# utilidong-butt-mk-1_1.net
KiCad netlist of a schematic drawn in EAGLE
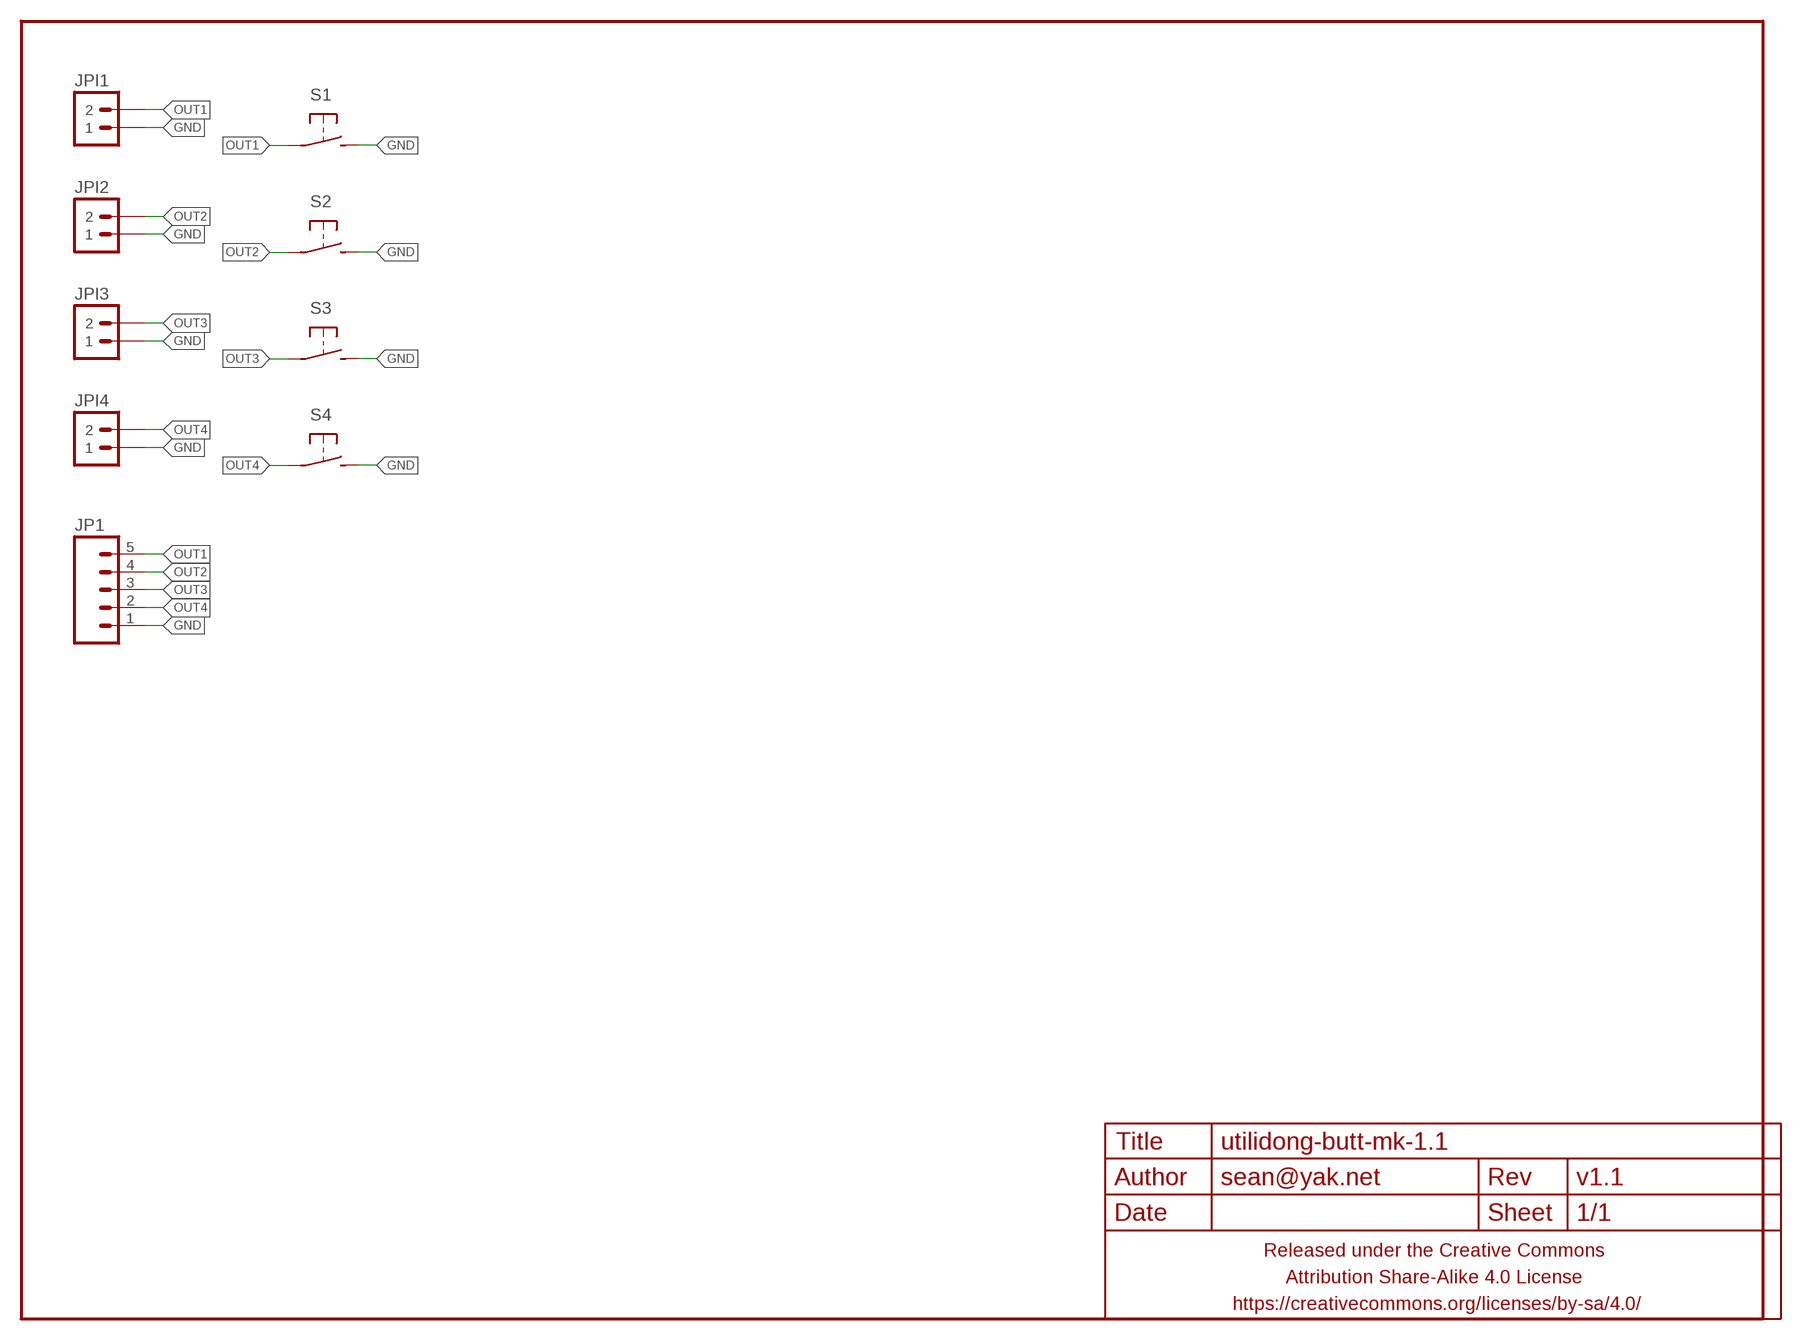
[diagram p0: schematic, sheet 1]

(export (version "E")
  (design (tool "Eeschema 10.0.6"))
  (components
    (comp (ref "FRAME1")
      (value "FRAME-LETTERNO_PACKAGE")
      (footprint "eagle-import:DUMMY")
      (fields (field (name "DESIGNER") "sean@yak.net") (field (name "VERSION") "v1.1"))
      (libsource (lib "eagle-import") (part "FRAME-LETTERNO_PACKAGE"))
    )
    (comp (ref "JP1")
      (value "M05JST-PH-VERT-PTH")
      (footprint "eagle-import:JST-5-PH-VERT-PTH")
      (libsource (lib "eagle-import") (part "M05JST-PH-VERT-PTH"))
    )
    (comp (ref "JPI1")
      (value "M02PTH-CENTERED")
      (footprint "eagle-import:1X02-CENTER")
      (libsource (lib "eagle-import") (part "M02PTH-CENTERED"))
    )
    (comp (ref "JPI2")
      (value "M02PTH-CENTERED")
      (footprint "eagle-import:1X02-CENTER")
      (libsource (lib "eagle-import") (part "M02PTH-CENTERED"))
    )
    (comp (ref "JPI3")
      (value "M02PTH-CENTERED")
      (footprint "eagle-import:1X02-CENTER")
      (libsource (lib "eagle-import") (part "M02PTH-CENTERED"))
    )
    (comp (ref "JPI4")
      (value "M02PTH-CENTERED")
      (footprint "eagle-import:1X02-CENTER")
      (libsource (lib "eagle-import") (part "M02PTH-CENTERED"))
    )
    (comp (ref "S1")
      (value "SPST-NO-TACT6MM-PTH-SMALL-PADS")
      (footprint "eagle-import:DTS-6-SMALL-PADS")
      (libsource (lib "eagle-import") (part "SPST-NO-TACT6MM-PTH-SMALL-PADS"))
    )
    (comp (ref "S2")
      (value "SPST-NO-TACT6MM-PTH-SMALL-PADS")
      (footprint "eagle-import:DTS-6-SMALL-PADS")
      (libsource (lib "eagle-import") (part "SPST-NO-TACT6MM-PTH-SMALL-PADS"))
    )
    (comp (ref "S3")
      (value "SPST-NO-TACT6MM-PTH-SMALL-PADS")
      (footprint "eagle-import:DTS-6-SMALL-PADS")
      (libsource (lib "eagle-import") (part "SPST-NO-TACT6MM-PTH-SMALL-PADS"))
    )
    (comp (ref "S4")
      (value "SPST-NO-TACT6MM-PTH-SMALL-PADS")
      (footprint "eagle-import:DTS-6-SMALL-PADS")
      (libsource (lib "eagle-import") (part "SPST-NO-TACT6MM-PTH-SMALL-PADS"))
    )
  )
  (nets
    (net (code "1") (name "GND") (class "Default")
      (node (ref "JP1") (pin "1") (pinfunction "1_1") (pintype "passive"))
      (node (ref "JPI1") (pin "1") (pinfunction "1_1") (pintype "passive"))
      (node (ref "JPI2") (pin "1") (pinfunction "1_1") (pintype "passive"))
      (node (ref "JPI3") (pin "1") (pinfunction "1_1") (pintype "passive"))
      (node (ref "JPI4") (pin "1") (pinfunction "1_1") (pintype "passive"))
      (node (ref "S1") (pin "3") (pinfunction "2_3") (pintype "passive"))
      (node (ref "S1") (pin "4") (pinfunction "2_4") (pintype "passive"))
      (node (ref "S2") (pin "3") (pinfunction "2_3") (pintype "passive"))
      (node (ref "S2") (pin "4") (pinfunction "2_4") (pintype "passive"))
      (node (ref "S3") (pin "3") (pinfunction "2_3") (pintype "passive"))
      (node (ref "S3") (pin "4") (pinfunction "2_4") (pintype "passive"))
      (node (ref "S4") (pin "3") (pinfunction "2_3") (pintype "passive"))
      (node (ref "S4") (pin "4") (pinfunction "2_4") (pintype "passive"))
    )
    (net (code "2") (name "OUT1") (class "Default")
      (node (ref "JP1") (pin "5") (pinfunction "5_5") (pintype "passive"))
      (node (ref "JPI1") (pin "2") (pinfunction "2_2") (pintype "passive"))
      (node (ref "S1") (pin "1") (pinfunction "1_1") (pintype "passive"))
      (node (ref "S1") (pin "2") (pinfunction "1_2") (pintype "passive"))
    )
    (net (code "3") (name "OUT2") (class "Default")
      (node (ref "JP1") (pin "4") (pinfunction "4_4") (pintype "passive"))
      (node (ref "JPI2") (pin "2") (pinfunction "2_2") (pintype "passive"))
      (node (ref "S2") (pin "1") (pinfunction "1_1") (pintype "passive"))
      (node (ref "S2") (pin "2") (pinfunction "1_2") (pintype "passive"))
    )
    (net (code "4") (name "OUT3") (class "Default")
      (node (ref "JP1") (pin "3") (pinfunction "3_3") (pintype "passive"))
      (node (ref "JPI3") (pin "2") (pinfunction "2_2") (pintype "passive"))
      (node (ref "S3") (pin "1") (pinfunction "1_1") (pintype "passive"))
      (node (ref "S3") (pin "2") (pinfunction "1_2") (pintype "passive"))
    )
    (net (code "5") (name "OUT4") (class "Default")
      (node (ref "JP1") (pin "2") (pinfunction "2_2") (pintype "passive"))
      (node (ref "JPI4") (pin "2") (pinfunction "2_2") (pintype "passive"))
      (node (ref "S4") (pin "1") (pinfunction "1_1") (pintype "passive"))
      (node (ref "S4") (pin "2") (pinfunction "1_2") (pintype "passive"))
    )
  )
)
